# STM32F103_PCB.net
KiCad netlist of a schematic drawn in EAGLE
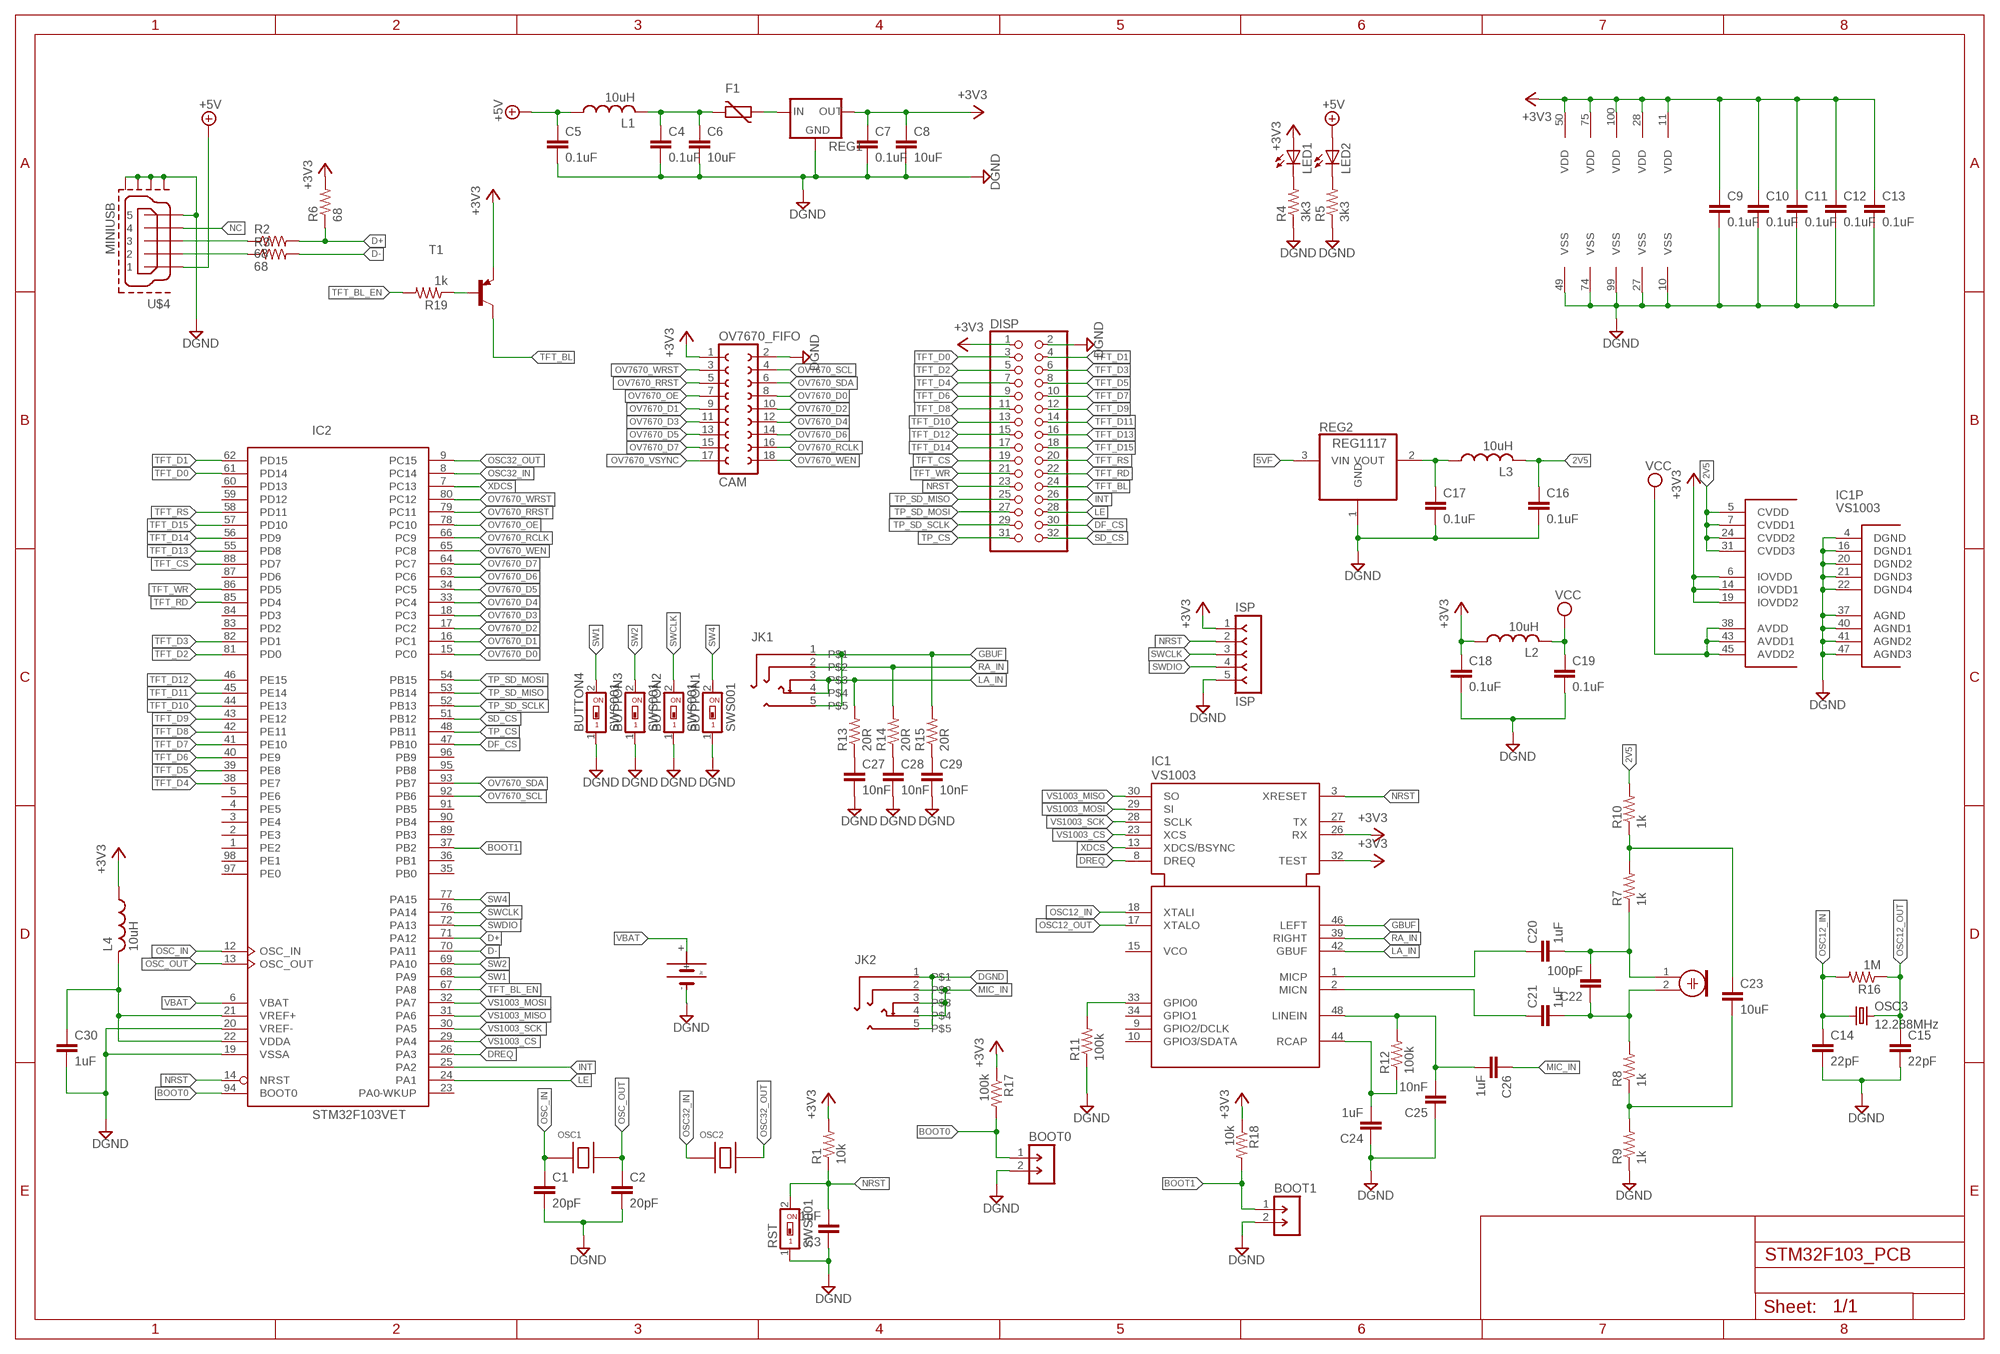
[diagram p0: schematic, sheet 1]

(export (version "E")
  (design (tool "Eeschema 10.0.6"))
  (components
    (comp (ref "BOOT0")
      (value "M-1X02-SIP-100-32")
      (footprint "eagle-import:SIP-100-02-32")
      (libsource (lib "eagle-import") (part "M-1X02-SIP-100-32"))
    )
    (comp (ref "BOOT1")
      (value "M-1X02-SIP-100-32")
      (footprint "eagle-import:SIP-100-02-32")
      (libsource (lib "eagle-import") (part "M-1X02-SIP-100-32"))
    )
    (comp (ref "BUTTON1")
      (value "SWS001")
      (footprint "eagle-import:SMS-001")
      (libsource (lib "eagle-import") (part "SWS001"))
    )
    (comp (ref "BUTTON2")
      (value "SWS001")
      (footprint "eagle-import:SMS-001")
      (libsource (lib "eagle-import") (part "SWS001"))
    )
    (comp (ref "BUTTON3")
      (value "SWS001")
      (footprint "eagle-import:SMS-001")
      (libsource (lib "eagle-import") (part "SWS001"))
    )
    (comp (ref "BUTTON4")
      (value "SWS001")
      (footprint "eagle-import:SMS-001")
      (libsource (lib "eagle-import") (part "SWS001"))
    )
    (comp (ref "C1")
      (value "20pF")
      (footprint "eagle-import:C1206")
      (libsource (lib "eagle-import") (part "C-EUC1206"))
    )
    (comp (ref "C2")
      (value "20pF")
      (footprint "eagle-import:C1206")
      (libsource (lib "eagle-import") (part "C-EUC1206"))
    )
    (comp (ref "C3")
      (value "1uF")
      (footprint "eagle-import:C1206")
      (libsource (lib "eagle-import") (part "C-EUC1206"))
    )
    (comp (ref "C4")
      (value "0.1uF")
      (footprint "eagle-import:C1206")
      (libsource (lib "eagle-import") (part "C-EUC1206"))
    )
    (comp (ref "C5")
      (value "0.1uF")
      (footprint "eagle-import:C1206")
      (libsource (lib "eagle-import") (part "C-EUC1206"))
    )
    (comp (ref "C6")
      (value "10uF")
      (footprint "eagle-import:C1206")
      (libsource (lib "eagle-import") (part "C-EUC1206"))
    )
    (comp (ref "C7")
      (value "0.1uF")
      (footprint "eagle-import:C1206")
      (libsource (lib "eagle-import") (part "C-EUC1206"))
    )
    (comp (ref "C8")
      (value "10uF")
      (footprint "eagle-import:C1206")
      (libsource (lib "eagle-import") (part "C-EUC1206"))
    )
    (comp (ref "C9")
      (value "0.1uF")
      (footprint "eagle-import:C1206")
      (libsource (lib "eagle-import") (part "C-EUC1206"))
    )
    (comp (ref "C10")
      (value "0.1uF")
      (footprint "eagle-import:C1206")
      (libsource (lib "eagle-import") (part "C-EUC1206"))
    )
    (comp (ref "C11")
      (value "0.1uF")
      (footprint "eagle-import:C1206")
      (libsource (lib "eagle-import") (part "C-EUC1206"))
    )
    (comp (ref "C12")
      (value "0.1uF")
      (footprint "eagle-import:C1206")
      (libsource (lib "eagle-import") (part "C-EUC1206"))
    )
    (comp (ref "C13")
      (value "0.1uF")
      (footprint "eagle-import:C1206")
      (libsource (lib "eagle-import") (part "C-EUC1206"))
    )
    (comp (ref "C14")
      (value "22pF")
      (footprint "eagle-import:C1206")
      (libsource (lib "eagle-import") (part "C-EUC1206"))
    )
    (comp (ref "C15")
      (value "22pF")
      (footprint "eagle-import:C1206")
      (libsource (lib "eagle-import") (part "C-EUC1206"))
    )
    (comp (ref "C16")
      (value "0.1uF")
      (footprint "eagle-import:C1206")
      (libsource (lib "eagle-import") (part "C-EUC1206"))
    )
    (comp (ref "C17")
      (value "0.1uF")
      (footprint "eagle-import:C1206")
      (libsource (lib "eagle-import") (part "C-EUC1206"))
    )
    (comp (ref "C18")
      (value "0.1uF")
      (footprint "eagle-import:C1206")
      (libsource (lib "eagle-import") (part "C-EUC1206"))
    )
    (comp (ref "C19")
      (value "0.1uF")
      (footprint "eagle-import:C1206")
      (libsource (lib "eagle-import") (part "C-EUC1206"))
    )
    (comp (ref "C20")
      (value "1uF")
      (footprint "eagle-import:C1206")
      (libsource (lib "eagle-import") (part "C-EUC1206"))
    )
    (comp (ref "C21")
      (value "1uF")
      (footprint "eagle-import:C1206")
      (libsource (lib "eagle-import") (part "C-EUC1206"))
    )
    (comp (ref "C22")
      (value "100pF")
      (footprint "eagle-import:C1206")
      (libsource (lib "eagle-import") (part "C-EUC1206"))
    )
    (comp (ref "C23")
      (value "10uF")
      (footprint "eagle-import:C1206")
      (libsource (lib "eagle-import") (part "C-EUC1206"))
    )
    (comp (ref "C24")
      (value "1uF")
      (footprint "eagle-import:C1206")
      (libsource (lib "eagle-import") (part "C-EUC1206"))
    )
    (comp (ref "C25")
      (value "10nF")
      (footprint "eagle-import:C1206")
      (libsource (lib "eagle-import") (part "C-EUC1206"))
    )
    (comp (ref "C26")
      (value "1uF")
      (footprint "eagle-import:C1206")
      (libsource (lib "eagle-import") (part "C-EUC1206"))
    )
    (comp (ref "C27")
      (value "10nF")
      (footprint "eagle-import:C1206")
      (libsource (lib "eagle-import") (part "C-EUC1206"))
    )
    (comp (ref "C28")
      (value "10nF")
      (footprint "eagle-import:C1206")
      (libsource (lib "eagle-import") (part "C-EUC1206"))
    )
    (comp (ref "C29")
      (value "10nF")
      (footprint "eagle-import:C1206")
      (libsource (lib "eagle-import") (part "C-EUC1206"))
    )
    (comp (ref "C30")
      (value "1uF")
      (footprint "eagle-import:C1206")
      (libsource (lib "eagle-import") (part "C-EUC1206"))
    )
    (comp (ref "CAM")
      (value "OV7670_FIFO")
      (footprint "eagle-import:FE09-2")
      (libsource (lib "eagle-import") (part "FE09-2"))
    )
    (comp (ref "DISP")
      (value "PINHD-2X16")
      (footprint "eagle-import:2X16")
      (libsource (lib "eagle-import") (part "PINHD-2X16"))
    )
    (comp (ref "F1")
      (value "VARISTORCN1206")
      (footprint "eagle-import:CT_CN1206")
      (libsource (lib "eagle-import") (part "VARISTORCN1206"))
    )
    (comp (ref "IC1")
      (value "VS1003")
      (footprint "eagle-import:LQFP48")
      (libsource (lib "eagle-import") (part "VS1003"))
    )
    (comp (ref "IC2")
      (value "STM32F103VET")
      (footprint "eagle-import:LQFP100")
      (libsource (lib "eagle-import") (part "STM32F103VTE"))
    )
    (comp (ref "ISP")
      (value "ISP")
      (footprint "eagle-import:SIP-100-05-40")
      (libsource (lib "eagle-import") (part "F-1X05-SIP-100-40"))
    )
    (comp (ref "JK1")
      (value "HEADPHONE_XXX1")
      (footprint "eagle-import:HEADPHONE_XXX1")
      (libsource (lib "eagle-import") (part "HEADPHONE_XXX1"))
    )
    (comp (ref "JK2")
      (value "HEADPHONE_XXX1")
      (footprint "eagle-import:HEADPHONE_XXX1")
      (libsource (lib "eagle-import") (part "HEADPHONE_XXX1"))
    )
    (comp (ref "L1")
      (value "10uH")
      (footprint "eagle-import:L3216C")
      (libsource (lib "eagle-import") (part "L-USL3216C"))
    )
    (comp (ref "L2")
      (value "10uH")
      (footprint "eagle-import:L3216C")
      (libsource (lib "eagle-import") (part "L-USL3216C"))
    )
    (comp (ref "L3")
      (value "10uH")
      (footprint "eagle-import:L3216C")
      (libsource (lib "eagle-import") (part "L-USL3216C"))
    )
    (comp (ref "L4")
      (value "10uH")
      (footprint "eagle-import:L3216C")
      (libsource (lib "eagle-import") (part "L-USL3216C"))
    )
    (comp (ref "LED1")
      (value "LEDSML1206")
      (footprint "eagle-import:SML1206")
      (libsource (lib "eagle-import") (part "LEDSML1206"))
    )
    (comp (ref "LED2")
      (value "LEDSML1206")
      (footprint "eagle-import:SML1206")
      (libsource (lib "eagle-import") (part "LEDSML1206"))
    )
    (comp (ref "MIC")
      (value "ELECTRET_MICROPHON-WM-61A")
      (footprint "eagle-import:WM-61A")
      (libsource (lib "eagle-import") (part "ELECTRET_MICROPHON-WM-61A"))
    )
    (comp (ref "OSC1")
      (value "8.0MHz")
      (footprint "eagle-import:IQG7050B")
      (libsource (lib "eagle-import") (part "SMCE-7050"))
    )
    (comp (ref "OSC2")
      (value "32.768kHz")
      (footprint "eagle-import:IQG5032A")
      (libsource (lib "eagle-import") (part "SMAQ-5032A"))
    )
    (comp (ref "OSC3")
      (value "12.288MHz")
      (footprint "eagle-import:HC49UP")
      (libsource (lib "eagle-import") (part "CRYSTALHC49UP"))
    )
    (comp (ref "R1")
      (value "10k")
      (footprint "eagle-import:R1206")
      (libsource (lib "eagle-import") (part "R-US_R1206"))
    )
    (comp (ref "R2")
      (value "68")
      (footprint "eagle-import:R1206")
      (libsource (lib "eagle-import") (part "R-US_R1206"))
    )
    (comp (ref "R3")
      (value "68")
      (footprint "eagle-import:R1206")
      (libsource (lib "eagle-import") (part "R-US_R1206"))
    )
    (comp (ref "R4")
      (value "3k3")
      (footprint "eagle-import:R1206")
      (libsource (lib "eagle-import") (part "R-US_R1206"))
    )
    (comp (ref "R5")
      (value "3k3")
      (footprint "eagle-import:R1206")
      (libsource (lib "eagle-import") (part "R-US_R1206"))
    )
    (comp (ref "R6")
      (value "68")
      (footprint "eagle-import:R1206")
      (libsource (lib "eagle-import") (part "R-US_R1206"))
    )
    (comp (ref "R7")
      (value "1k")
      (footprint "eagle-import:R1206")
      (libsource (lib "eagle-import") (part "R-US_R1206"))
    )
    (comp (ref "R8")
      (value "1k")
      (footprint "eagle-import:R1206")
      (libsource (lib "eagle-import") (part "R-US_R1206"))
    )
    (comp (ref "R9")
      (value "1k")
      (footprint "eagle-import:R1206")
      (libsource (lib "eagle-import") (part "R-US_R1206"))
    )
    (comp (ref "R10")
      (value "1k")
      (footprint "eagle-import:R1206")
      (libsource (lib "eagle-import") (part "R-US_R1206"))
    )
    (comp (ref "R11")
      (value "100k")
      (footprint "eagle-import:R1206")
      (libsource (lib "eagle-import") (part "R-US_R1206"))
    )
    (comp (ref "R12")
      (value "100k")
      (footprint "eagle-import:R1206")
      (libsource (lib "eagle-import") (part "R-US_R1206"))
    )
    (comp (ref "R13")
      (value "20R")
      (footprint "eagle-import:R1206")
      (libsource (lib "eagle-import") (part "R-US_R1206"))
    )
    (comp (ref "R14")
      (value "20R")
      (footprint "eagle-import:R1206")
      (libsource (lib "eagle-import") (part "R-US_R1206"))
    )
    (comp (ref "R15")
      (value "20R")
      (footprint "eagle-import:R1206")
      (libsource (lib "eagle-import") (part "R-US_R1206"))
    )
    (comp (ref "R16")
      (value "1M")
      (footprint "eagle-import:R1206")
      (libsource (lib "eagle-import") (part "R-US_R1206"))
    )
    (comp (ref "R17")
      (value "100k")
      (footprint "eagle-import:R1206")
      (libsource (lib "eagle-import") (part "R-US_R1206"))
    )
    (comp (ref "R18")
      (value "10k")
      (footprint "eagle-import:R1206")
      (libsource (lib "eagle-import") (part "R-US_R1206"))
    )
    (comp (ref "R19")
      (value "1k")
      (footprint "eagle-import:R1206")
      (libsource (lib "eagle-import") (part "R-US_R1206"))
    )
    (comp (ref "REG1")
      (value "XC63FPM")
      (footprint "eagle-import:SOT23")
      (libsource (lib "eagle-import") (part "XC63FPM"))
    )
    (comp (ref "REG2")
      (value "REG1117")
      (footprint "eagle-import:SOT223")
      (libsource (lib "eagle-import") (part "REG1117"))
    )
    (comp (ref "RST")
      (value "SWS001")
      (footprint "eagle-import:SMS-001")
      (libsource (lib "eagle-import") (part "SWS001"))
    )
    (comp (ref "T1")
      (value "MMBT3906LT1-PNP-SOT23-BEC")
      (footprint "eagle-import:SOT23-BEC")
      (libsource (lib "eagle-import") (part "-PNP-SOT23-BECMMBT3906LT1"))
    )
    (comp (ref "U$1")
      (value "1220BATTERY_SF")
      (footprint "eagle-import:1220BATTERY")
      (libsource (lib "eagle-import") (part "1220BATTERY_SF"))
    )
    (comp (ref "U$4")
      (value "MINIUSB")
      (footprint "eagle-import:MK5P")
      (libsource (lib "eagle-import") (part "MINIUSB"))
    )
  )
  (nets
    (net (code "1") (name "+3V3") (class "Default")
      (node (ref "C10") (pin "1") (pinfunction "1_1") (pintype "passive"))
      (node (ref "C11") (pin "1") (pinfunction "1_1") (pintype "passive"))
      (node (ref "C12") (pin "1") (pinfunction "1_1") (pintype "passive"))
      (node (ref "C13") (pin "1") (pinfunction "1_1") (pintype "passive"))
      (node (ref "C18") (pin "1") (pinfunction "1_1") (pintype "passive"))
      (node (ref "C7") (pin "1") (pinfunction "1_1") (pintype "passive"))
      (node (ref "C8") (pin "1") (pinfunction "1_1") (pintype "passive"))
      (node (ref "C9") (pin "1") (pinfunction "1_1") (pintype "passive"))
      (node (ref "CAM") (pin "1") (pinfunction "1_1") (pintype "passive"))
      (node (ref "DISP") (pin "1") (pinfunction "1_1") (pintype "passive"))
      (node (ref "IC1") (pin "14") (pinfunction "IOVDD1_14") (pintype "power_in"))
      (node (ref "IC1") (pin "19") (pinfunction "IOVDD2_19") (pintype "power_in"))
      (node (ref "IC1") (pin "26") (pinfunction "RX_26") (pintype "bidirectional"))
      (node (ref "IC1") (pin "32") (pinfunction "TEST_32") (pintype "bidirectional"))
      (node (ref "IC1") (pin "6") (pinfunction "IOVDD_6") (pintype "power_in"))
      (node (ref "IC2") (pin "100") (pinfunction "VDD_100") (pintype "power_in"))
      (node (ref "IC2") (pin "11") (pinfunction "VDD_11") (pintype "power_in"))
      (node (ref "IC2") (pin "28") (pinfunction "VDD_28") (pintype "power_in"))
      (node (ref "IC2") (pin "50") (pinfunction "VDD_50") (pintype "power_in"))
      (node (ref "IC2") (pin "75") (pinfunction "VDD_75") (pintype "power_in"))
      (node (ref "ISP") (pin "1") (pinfunction "1_1") (pintype "passive"))
      (node (ref "L2") (pin "1") (pinfunction "1_1") (pintype "passive"))
      (node (ref "L4") (pin "1") (pinfunction "1_1") (pintype "passive"))
      (node (ref "LED1") (pin "A") (pinfunction "A_A") (pintype "passive"))
      (node (ref "R1") (pin "2") (pinfunction "2_2") (pintype "passive"))
      (node (ref "R17") (pin "1") (pinfunction "1_1") (pintype "passive"))
      (node (ref "R18") (pin "1") (pinfunction "1_1") (pintype "passive"))
      (node (ref "R6") (pin "2") (pinfunction "2_2") (pintype "passive"))
      (node (ref "REG1") (pin "2") (pinfunction "OUT_2") (pintype "passive"))
      (node (ref "T1") (pin "E") (pinfunction "E_E") (pintype "passive"))
    )
    (net (code "2") (name "+5V") (class "Default")
      (node (ref "C5") (pin "1") (pinfunction "1_1") (pintype "passive"))
      (node (ref "L1") (pin "1") (pinfunction "1_1") (pintype "passive"))
      (node (ref "LED2") (pin "A") (pinfunction "A_A") (pintype "passive"))
      (node (ref "U$4") (pin "1") (pinfunction "1_1") (pintype "input"))
    )
    (net (code "3") (name "2V5") (class "Default")
      (node (ref "C16") (pin "1") (pinfunction "1_1") (pintype "passive"))
      (node (ref "IC1") (pin "24") (pinfunction "CVDD2_24") (pintype "power_in"))
      (node (ref "IC1") (pin "31") (pinfunction "CVDD3_31") (pintype "power_in"))
      (node (ref "IC1") (pin "5") (pinfunction "CVDD_5") (pintype "power_in"))
      (node (ref "IC1") (pin "7") (pinfunction "CVDD1_7") (pintype "power_in"))
      (node (ref "L3") (pin "2") (pinfunction "2_2") (pintype "passive"))
      (node (ref "R10") (pin "2") (pinfunction "2_2") (pintype "passive"))
    )
    (net (code "4") (name "5VF") (class "Default")
      (node (ref "F1") (pin "1") (pinfunction "1_1") (pintype "passive"))
      (node (ref "REG1") (pin "3") (pinfunction "IN_3") (pintype "input"))
      (node (ref "REG2") (pin "3") (pinfunction "VIN_3") (pintype "input"))
    )
    (net (code "5") (name "BOOT0") (class "Default")
      (node (ref "BOOT0") (pin "1") (pinfunction "1_1") (pintype "passive"))
      (node (ref "IC2") (pin "94") (pinfunction "BOOT0_94") (pintype "input"))
      (node (ref "R17") (pin "2") (pinfunction "2_2") (pintype "passive"))
    )
    (net (code "6") (name "BOOT1") (class "Default")
      (node (ref "BOOT1") (pin "1") (pinfunction "1_1") (pintype "passive"))
      (node (ref "IC2") (pin "37") (pinfunction "PB2_37") (pintype "bidirectional"))
      (node (ref "R18") (pin "2") (pinfunction "2_2") (pintype "passive"))
    )
    (net (code "7") (name "D+") (class "Default")
      (node (ref "IC2") (pin "71") (pinfunction "PA12_71") (pintype "bidirectional"))
      (node (ref "R2") (pin "2") (pinfunction "2_2") (pintype "passive"))
      (node (ref "R6") (pin "1") (pinfunction "1_1") (pintype "passive"))
    )
    (net (code "8") (name "D-") (class "Default")
      (node (ref "IC2") (pin "70") (pinfunction "PA11_70") (pintype "bidirectional"))
      (node (ref "R3") (pin "2") (pinfunction "2_2") (pintype "passive"))
    )
    (net (code "9") (name "DF_CS") (class "Default")
      (node (ref "DISP") (pin "30") (pinfunction "30_30") (pintype "passive"))
      (node (ref "IC2") (pin "47") (pinfunction "PB10_47") (pintype "bidirectional"))
    )
    (net (code "10") (name "DGND") (class "Default")
      (node (ref "BOOT0") (pin "2") (pinfunction "2_2") (pintype "passive"))
      (node (ref "BOOT1") (pin "2") (pinfunction "2_2") (pintype "passive"))
      (node (ref "BUTTON1") (pin "1") (pinfunction "1_1") (pintype "passive"))
      (node (ref "BUTTON2") (pin "1") (pinfunction "1_1") (pintype "passive"))
      (node (ref "BUTTON3") (pin "1") (pinfunction "1_1") (pintype "passive"))
      (node (ref "BUTTON4") (pin "1") (pinfunction "1_1") (pintype "passive"))
      (node (ref "C1") (pin "2") (pinfunction "2_2") (pintype "passive"))
      (node (ref "C10") (pin "2") (pinfunction "2_2") (pintype "passive"))
      (node (ref "C11") (pin "2") (pinfunction "2_2") (pintype "passive"))
      (node (ref "C12") (pin "2") (pinfunction "2_2") (pintype "passive"))
      (node (ref "C13") (pin "2") (pinfunction "2_2") (pintype "passive"))
      (node (ref "C14") (pin "2") (pinfunction "2_2") (pintype "passive"))
      (node (ref "C15") (pin "2") (pinfunction "2_2") (pintype "passive"))
      (node (ref "C16") (pin "2") (pinfunction "2_2") (pintype "passive"))
      (node (ref "C17") (pin "2") (pinfunction "2_2") (pintype "passive"))
      (node (ref "C18") (pin "2") (pinfunction "2_2") (pintype "passive"))
      (node (ref "C19") (pin "2") (pinfunction "2_2") (pintype "passive"))
      (node (ref "C2") (pin "2") (pinfunction "2_2") (pintype "passive"))
      (node (ref "C24") (pin "1") (pinfunction "1_1") (pintype "passive"))
      (node (ref "C25") (pin "1") (pinfunction "1_1") (pintype "passive"))
      (node (ref "C27") (pin "2") (pinfunction "2_2") (pintype "passive"))
      (node (ref "C28") (pin "2") (pinfunction "2_2") (pintype "passive"))
      (node (ref "C29") (pin "2") (pinfunction "2_2") (pintype "passive"))
      (node (ref "C3") (pin "1") (pinfunction "1_1") (pintype "passive"))
      (node (ref "C30") (pin "2") (pinfunction "2_2") (pintype "passive"))
      (node (ref "C4") (pin "2") (pinfunction "2_2") (pintype "passive"))
      (node (ref "C5") (pin "2") (pinfunction "2_2") (pintype "passive"))
      (node (ref "C6") (pin "2") (pinfunction "2_2") (pintype "passive"))
      (node (ref "C7") (pin "2") (pinfunction "2_2") (pintype "passive"))
      (node (ref "C8") (pin "2") (pinfunction "2_2") (pintype "passive"))
      (node (ref "C9") (pin "2") (pinfunction "2_2") (pintype "passive"))
      (node (ref "CAM") (pin "2") (pinfunction "2_2") (pintype "passive"))
      (node (ref "DISP") (pin "2") (pinfunction "2_2") (pintype "passive"))
      (node (ref "IC1") (pin "16") (pinfunction "DGND1_16") (pintype "power_in"))
      (node (ref "IC1") (pin "20") (pinfunction "DGND2_20") (pintype "power_in"))
      (node (ref "IC1") (pin "21") (pinfunction "DGND3_21") (pintype "power_in"))
      (node (ref "IC1") (pin "22") (pinfunction "DGND4_22") (pintype "power_in"))
      (node (ref "IC1") (pin "37") (pinfunction "AGND_37") (pintype "power_in"))
      (node (ref "IC1") (pin "4") (pinfunction "DGND_4") (pintype "power_in"))
      (node (ref "IC1") (pin "40") (pinfunction "AGND1_40") (pintype "power_in"))
      (node (ref "IC1") (pin "41") (pinfunction "AGND2_41") (pintype "power_in"))
      (node (ref "IC1") (pin "47") (pinfunction "AGND3_47") (pintype "power_in"))
      (node (ref "IC2") (pin "10") (pinfunction "VSS_10") (pintype "power_in"))
      (node (ref "IC2") (pin "19") (pinfunction "VSSA_19") (pintype "power_in"))
      (node (ref "IC2") (pin "20") (pinfunction "VREF-_20") (pintype "power_in"))
      (node (ref "IC2") (pin "27") (pinfunction "VSS_27") (pintype "power_in"))
      (node (ref "IC2") (pin "49") (pinfunction "VSS_49") (pintype "power_in"))
      (node (ref "IC2") (pin "74") (pinfunction "VSS_74") (pintype "power_in"))
      (node (ref "IC2") (pin "99") (pinfunction "VSS_99") (pintype "power_in"))
      (node (ref "ISP") (pin "5") (pinfunction "5_5") (pintype "passive"))
      (node (ref "JK2") (pin "1") (pinfunction "P$1_1") (pintype "bidirectional"))
      (node (ref "JK2") (pin "5") (pinfunction "P$5_5") (pintype "bidirectional"))
      (node (ref "R11") (pin "1") (pinfunction "1_1") (pintype "passive"))
      (node (ref "R4") (pin "1") (pinfunction "1_1") (pintype "passive"))
      (node (ref "R5") (pin "1") (pinfunction "1_1") (pintype "passive"))
      (node (ref "R9") (pin "1") (pinfunction "1_1") (pintype "passive"))
      (node (ref "REG1") (pin "1") (pinfunction "GND_1") (pintype "input"))
      (node (ref "REG2") (pin "1") (pinfunction "GND_1") (pintype "power_in"))
      (node (ref "RST") (pin "1") (pinfunction "1_1") (pintype "passive"))
      (node (ref "U$1") (pin "-") (pinfunction "-_-") (pintype "bidirectional"))
      (node (ref "U$4") (pin "5") (pinfunction "5_5") (pintype "input"))
      (node (ref "U$4") (pin "P$1") (pinfunction "GND1_P$1") (pintype "bidirectional"))
      (node (ref "U$4") (pin "P$2") (pinfunction "GND2_P$2") (pintype "bidirectional"))
      (node (ref "U$4") (pin "P$6") (pinfunction "GND3_P$6") (pintype "bidirectional"))
      (node (ref "U$4") (pin "P$7") (pinfunction "GND4_P$7") (pintype "bidirectional"))
    )
    (net (code "11") (name "DREQ") (class "Default")
      (node (ref "IC1") (pin "8") (pinfunction "DREQ_8") (pintype "bidirectional"))
      (node (ref "IC2") (pin "26") (pinfunction "PA3_26") (pintype "bidirectional"))
    )
    (net (code "12") (name "GBUF") (class "Default")
      (node (ref "IC1") (pin "46") (pinfunction "LEFT_46") (pintype "bidirectional"))
      (node (ref "JK1") (pin "1") (pinfunction "P$1_1") (pintype "bidirectional"))
      (node (ref "JK1") (pin "5") (pinfunction "P$5_5") (pintype "bidirectional"))
      (node (ref "R15") (pin "2") (pinfunction "2_2") (pintype "passive"))
    )
    (net (code "13") (name "INT") (class "Default")
      (node (ref "DISP") (pin "26") (pinfunction "26_26") (pintype "passive"))
      (node (ref "IC2") (pin "25") (pinfunction "PA2_25") (pintype "bidirectional"))
    )
    (net (code "14") (name "LA_IN") (class "Default")
      (node (ref "IC1") (pin "42") (pinfunction "GBUF_42") (pintype "bidirectional"))
      (node (ref "JK1") (pin "3") (pinfunction "P$3_3") (pintype "bidirectional"))
      (node (ref "JK1") (pin "4") (pinfunction "P$4_4") (pintype "bidirectional"))
      (node (ref "R13") (pin "2") (pinfunction "2_2") (pintype "passive"))
    )
    (net (code "15") (name "LE") (class "Default")
      (node (ref "DISP") (pin "28") (pinfunction "28_28") (pintype "passive"))
      (node (ref "IC2") (pin "24") (pinfunction "PA1_24") (pintype "bidirectional"))
    )
    (net (code "16") (name "MIC_IN") (class "Default")
      (node (ref "C26") (pin "1") (pinfunction "1_1") (pintype "passive"))
      (node (ref "JK2") (pin "2") (pinfunction "P$2_2") (pintype "bidirectional"))
      (node (ref "JK2") (pin "3") (pinfunction "P$3_3") (pintype "bidirectional"))
      (node (ref "JK2") (pin "4") (pinfunction "P$4_4") (pintype "bidirectional"))
    )
    (net (code "17") (name "NC") (class "Default")
      (node (ref "U$4") (pin "4") (pinfunction "4_4") (pintype "input"))
    )
    (net (code "18") (name "NRST") (class "Default")
      (node (ref "C3") (pin "2") (pinfunction "2_2") (pintype "passive"))
      (node (ref "DISP") (pin "23") (pinfunction "23_23") (pintype "passive"))
      (node (ref "IC1") (pin "3") (pinfunction "XRESET_3") (pintype "bidirectional"))
      (node (ref "IC2") (pin "14") (pinfunction "NRST_14") (pintype "bidirectional"))
      (node (ref "ISP") (pin "2") (pinfunction "2_2") (pintype "passive"))
      (node (ref "R1") (pin "1") (pinfunction "1_1") (pintype "passive"))
      (node (ref "RST") (pin "2") (pinfunction "2_2") (pintype "passive"))
    )
    (net (code "19") (name "Net-(C4-Pad1)") (class "Default")
      (node (ref "C4") (pin "1") (pinfunction "1_1") (pintype "passive"))
      (node (ref "C6") (pin "1") (pinfunction "1_1") (pintype "passive"))
      (node (ref "F1") (pin "2") (pinfunction "2_2") (pintype "passive"))
      (node (ref "L1") (pin "2") (pinfunction "2_2") (pintype "passive"))
    )
    (net (code "20") (name "Net-(C20-Pad2)") (class "Default")
      (node (ref "C20") (pin "2") (pinfunction "2_2") (pintype "passive"))
      (node (ref "C22") (pin "2") (pinfunction "2_2") (pintype "passive"))
      (node (ref "MIC") (pin "1") (pinfunction "1_1") (pintype "passive"))
      (node (ref "R7") (pin "1") (pinfunction "1_1") (pintype "passive"))
    )
    (net (code "21") (name "Net-(C21-Pad2)") (class "Default")
      (node (ref "C21") (pin "2") (pinfunction "2_2") (pintype "passive"))
      (node (ref "C22") (pin "1") (pinfunction "1_1") (pintype "passive"))
      (node (ref "MIC") (pin "2") (pinfunction "2_2") (pintype "passive"))
      (node (ref "R8") (pin "2") (pinfunction "2_2") (pintype "passive"))
    )
    (net (code "22") (name "Net-(C23-Pad1)") (class "Default")
      (node (ref "C23") (pin "1") (pinfunction "1_1") (pintype "passive"))
      (node (ref "R10") (pin "1") (pinfunction "1_1") (pintype "passive"))
      (node (ref "R7") (pin "2") (pinfunction "2_2") (pintype "passive"))
    )
    (net (code "23") (name "Net-(C23-Pad2)") (class "Default")
      (node (ref "C23") (pin "2") (pinfunction "2_2") (pintype "passive"))
      (node (ref "R8") (pin "1") (pinfunction "1_1") (pintype "passive"))
      (node (ref "R9") (pin "2") (pinfunction "2_2") (pintype "passive"))
    )
    (net (code "24") (name "Net-(C27-Pad1)") (class "Default")
      (node (ref "C27") (pin "1") (pinfunction "1_1") (pintype "passive"))
      (node (ref "R13") (pin "1") (pinfunction "1_1") (pintype "passive"))
    )
    (net (code "25") (name "Net-(C28-Pad1)") (class "Default")
      (node (ref "C28") (pin "1") (pinfunction "1_1") (pintype "passive"))
      (node (ref "R14") (pin "1") (pinfunction "1_1") (pintype "passive"))
    )
    (net (code "26") (name "Net-(C29-Pad1)") (class "Default")
      (node (ref "C29") (pin "1") (pinfunction "1_1") (pintype "passive"))
      (node (ref "R15") (pin "1") (pinfunction "1_1") (pintype "passive"))
    )
    (net (code "27") (name "Net-(IC1A-GPIO0)") (class "Default")
      (node (ref "IC1") (pin "33") (pinfunction "GPIO0_33") (pintype "bidirectional"))
      (node (ref "R11") (pin "2") (pinfunction "2_2") (pintype "passive"))
    )
    (net (code "28") (name "Net-(IC1A-LINEIN)") (class "Default")
      (node (ref "C25") (pin "2") (pinfunction "2_2") (pintype "passive"))
      (node (ref "C26") (pin "2") (pinfunction "2_2") (pintype "passive"))
      (node (ref "IC1") (pin "48") (pinfunction "LINEIN_48") (pintype "bidirectional"))
      (node (ref "R12") (pin "2") (pinfunction "2_2") (pintype "passive"))
    )
    (net (code "29") (name "Net-(IC1A-MICN)") (class "Default")
      (node (ref "C21") (pin "1") (pinfunction "1_1") (pintype "passive"))
      (node (ref "IC1") (pin "2") (pinfunction "MICN_2") (pintype "bidirectional"))
    )
    (net (code "30") (name "Net-(IC1A-MICP)") (class "Default")
      (node (ref "C20") (pin "1") (pinfunction "1_1") (pintype "passive"))
      (node (ref "IC1") (pin "1") (pinfunction "MICP_1") (pintype "bidirectional"))
    )
    (net (code "31") (name "Net-(IC1A-RCAP)") (class "Default")
      (node (ref "C24") (pin "2") (pinfunction "2_2") (pintype "passive"))
      (node (ref "IC1") (pin "44") (pinfunction "RCAP_44") (pintype "bidirectional"))
      (node (ref "R12") (pin "1") (pinfunction "1_1") (pintype "passive"))
    )
    (net (code "32") (name "Net-(IC2A-VDDA)") (class "Default")
      (node (ref "C30") (pin "1") (pinfunction "1_1") (pintype "passive"))
      (node (ref "IC2") (pin "21") (pinfunction "VREF+_21") (pintype "power_in"))
      (node (ref "IC2") (pin "22") (pinfunction "VDDA_22") (pintype "power_in"))
      (node (ref "L4") (pin "2") (pinfunction "2_2") (pintype "passive"))
    )
    (net (code "33") (name "Net-(LED1-PadC)") (class "Default")
      (node (ref "LED1") (pin "C") (pinfunction "C_C") (pintype "passive"))
      (node (ref "R4") (pin "2") (pinfunction "2_2") (pintype "passive"))
    )
    (net (code "34") (name "Net-(LED2-PadC)") (class "Default")
      (node (ref "LED2") (pin "C") (pinfunction "C_C") (pintype "passive"))
      (node (ref "R5") (pin "2") (pinfunction "2_2") (pintype "passive"))
    )
    (net (code "35") (name "Net-(R2-Pad1)") (class "Default")
      (node (ref "R2") (pin "1") (pinfunction "1_1") (pintype "passive"))
      (node (ref "U$4") (pin "3") (pinfunction "3_3") (pintype "input"))
    )
    (net (code "36") (name "Net-(R3-Pad1)") (class "Default")
      (node (ref "R3") (pin "1") (pinfunction "1_1") (pintype "passive"))
      (node (ref "U$4") (pin "2") (pinfunction "2_2") (pintype "input"))
    )
    (net (code "37") (name "Net-(R19-Pad1)") (class "Default")
      (node (ref "R19") (pin "1") (pinfunction "1_1") (pintype "passive"))
      (node (ref "T1") (pin "B") (pinfunction "B_B") (pintype "passive"))
    )
    (net (code "38") (name "Net-(REG2-VOUT)") (class "Default")
      (node (ref "C17") (pin "1") (pinfunction "1_1") (pintype "passive"))
      (node (ref "L3") (pin "1") (pinfunction "1_1") (pintype "passive"))
      (node (ref "REG2") (pin "2") (pinfunction "VOUT_2") (pintype "output"))
    )
    (net (code "39") (name "OSC12_IN") (class "Default")
      (node (ref "C14") (pin "1") (pinfunction "1_1") (pintype "passive"))
      (node (ref "IC1") (pin "18") (pinfunction "XTALI_18") (pintype "bidirectional"))
      (node (ref "OSC3") (pin "1") (pinfunction "1_1") (pintype "passive"))
      (node (ref "R16") (pin "2") (pinfunction "2_2") (pintype "passive"))
    )
    (net (code "40") (name "OSC12_OUT") (class "Default")
      (node (ref "C15") (pin "1") (pinfunction "1_1") (pintype "passive"))
      (node (ref "IC1") (pin "17") (pinfunction "XTALO_17") (pintype "bidirectional"))
      (node (ref "OSC3") (pin "2") (pinfunction "2_2") (pintype "passive"))
      (node (ref "R16") (pin "1") (pinfunction "1_1") (pintype "passive"))
    )
    (net (code "41") (name "OSC32_IN") (class "Default")
      (node (ref "IC2") (pin "8") (pinfunction "PC14_8") (pintype "bidirectional"))
      (node (ref "OSC2") (pin "P$1") (pinfunction "PIN1_P$1") (pintype "bidirectional"))
    )
    (net (code "42") (name "OSC32_OUT") (class "Default")
      (node (ref "IC2") (pin "9") (pinfunction "PC15_9") (pintype "bidirectional"))
      (node (ref "OSC2") (pin "P$2") (pinfunction "PIN2_P$2") (pintype "bidirectional"))
    )
    (net (code "43") (name "OSC_IN") (class "Default")
      (node (ref "C1") (pin "1") (pinfunction "1_1") (pintype "passive"))
      (node (ref "IC2") (pin "12") (pinfunction "OSC_IN_12") (pintype "bidirectional"))
      (node (ref "OSC1") (pin "P$1") (pinfunction "PIN1_P$1") (pintype "bidirectional"))
    )
    (net (code "44") (name "OSC_OUT") (class "Default")
      (node (ref "C2") (pin "1") (pinfunction "1_1") (pintype "passive"))
      (node (ref "IC2") (pin "13") (pinfunction "OSC_OUT_13") (pintype "bidirectional"))
      (node (ref "OSC1") (pin "P$3") (pinfunction "PIN2_P$3") (pintype "bidirectional"))
    )
    (net (code "45") (name "OV7670_D0") (class "Default")
      (node (ref "CAM") (pin "8") (pinfunction "8_8") (pintype "passive"))
      (node (ref "IC2") (pin "15") (pinfunction "PC0_15") (pintype "bidirectional"))
    )
    (net (code "46") (name "OV7670_D1") (class "Default")
      (node (ref "CAM") (pin "9") (pinfunction "9_9") (pintype "passive"))
      (node (ref "IC2") (pin "16") (pinfunction "PC1_16") (pintype "bidirectional"))
    )
    (net (code "47") (name "OV7670_D2") (class "Default")
      (node (ref "CAM") (pin "10") (pinfunction "10_10") (pintype "passive"))
      (node (ref "IC2") (pin "17") (pinfunction "PC2_17") (pintype "bidirectional"))
    )
    (net (code "48") (name "OV7670_D3") (class "Default")
      (node (ref "CAM") (pin "11") (pinfunction "11_11") (pintype "passive"))
      (node (ref "IC2") (pin "18") (pinfunction "PC3_18") (pintype "bidirectional"))
    )
    (net (code "49") (name "OV7670_D4") (class "Default")
      (node (ref "CAM") (pin "12") (pinfunction "12_12") (pintype "passive"))
      (node (ref "IC2") (pin "33") (pinfunction "PC4_33") (pintype "bidirectional"))
    )
    (net (code "50") (name "OV7670_D5") (class "Default")
      (node (ref "CAM") (pin "13") (pinfunction "13_13") (pintype "passive"))
      (node (ref "IC2") (pin "34") (pinfunction "PC5_34") (pintype "bidirectional"))
    )
    (net (code "51") (name "OV7670_D6") (class "Default")
      (node (ref "CAM") (pin "14") (pinfunction "14_14") (pintype "passive"))
      (node (ref "IC2") (pin "63") (pinfunction "PC6_63") (pintype "bidirectional"))
    )
    (net (code "52") (name "OV7670_D7") (class "Default")
      (node (ref "CAM") (pin "15") (pinfunction "15_15") (pintype "passive"))
      (node (ref "IC2") (pin "64") (pinfunction "PC7_64") (pintype "bidirectional"))
    )
    (net (code "53") (name "OV7670_OE") (class "Default")
      (node (ref "CAM") (pin "7") (pinfunction "7_7") (pintype "passive"))
      (node (ref "IC2") (pin "78") (pinfunction "PC10_78") (pintype "bidirectional"))
    )
    (net (code "54") (name "OV7670_RCLK") (class "Default")
      (node (ref "CAM") (pin "16") (pinfunction "16_16") (pintype "passive"))
      (node (ref "IC2") (pin "66") (pinfunction "PC9_66") (pintype "bidirectional"))
    )
    (net (code "55") (name "OV7670_RRST") (class "Default")
      (node (ref "CAM") (pin "5") (pinfunction "5_5") (pintype "passive"))
      (node (ref "IC2") (pin "79") (pinfunction "PC11_79") (pintype "bidirectional"))
    )
    (net (code "56") (name "OV7670_SCL") (class "Default")
      (node (ref "CAM") (pin "4") (pinfunction "4_4") (pintype "passive"))
      (node (ref "IC2") (pin "92") (pinfunction "PB6_92") (pintype "bidirectional"))
    )
    (net (code "57") (name "OV7670_SDA") (class "Default")
      (node (ref "CAM") (pin "6") (pinfunction "6_6") (pintype "passive"))
      (node (ref "IC2") (pin "93") (pinfunction "PB7_93") (pintype "bidirectional"))
    )
    (net (code "58") (name "OV7670_VSYNC") (class "Default")
      (node (ref "CAM") (pin "17") (pinfunction "17_17") (pintype "passive"))
    )
    (net (code "59") (name "OV7670_WEN") (class "Default")
      (node (ref "CAM") (pin "18") (pinfunction "18_18") (pintype "passive"))
      (node (ref "IC2") (pin "65") (pinfunction "PC8_65") (pintype "bidirectional"))
    )
    (net (code "60") (name "OV7670_WRST") (class "Default")
      (node (ref "CAM") (pin "3") (pinfunction "3_3") (pintype "passive"))
      (node (ref "IC2") (pin "80") (pinfunction "PC12_80") (pintype "bidirectional"))
    )
    (net (code "61") (name "RA_IN") (class "Default")
      (node (ref "IC1") (pin "39") (pinfunction "RIGHT_39") (pintype "bidirectional"))
      (node (ref "JK1") (pin "2") (pinfunction "P$2_2") (pintype "bidirectional"))
      (node (ref "R14") (pin "2") (pinfunction "2_2") (pintype "passive"))
    )
    (net (code "62") (name "SD_CS") (class "Default")
      (node (ref "DISP") (pin "32") (pinfunction "32_32") (pintype "passive"))
      (node (ref "IC2") (pin "51") (pinfunction "PB12_51") (pintype "bidirectional"))
    )
    (net (code "63") (name "SW1") (class "Default")
      (node (ref "BUTTON4") (pin "2") (pinfunction "2_2") (pintype "passive"))
      (node (ref "IC2") (pin "68") (pinfunction "PA9_68") (pintype "bidirectional"))
    )
    (net (code "64") (name "SW2") (class "Default")
      (node (ref "BUTTON3") (pin "2") (pinfunction "2_2") (pintype "passive"))
      (node (ref "IC2") (pin "69") (pinfunction "PA10_69") (pintype "bidirectional"))
    )
    (net (code "65") (name "SW4") (class "Default")
      (node (ref "BUTTON1") (pin "2") (pinfunction "2_2") (pintype "passive"))
      (node (ref "IC2") (pin "77") (pinfunction "PA15_77") (pintype "bidirectional"))
    )
    (net (code "66") (name "SWCLK") (class "Default")
      (node (ref "BUTTON2") (pin "2") (pinfunction "2_2") (pintype "passive"))
      (node (ref "IC2") (pin "76") (pinfunction "PA14_76") (pintype "bidirectional"))
      (node (ref "ISP") (pin "3") (pinfunction "3_3") (pintype "passive"))
    )
    (net (code "67") (name "SWDIO") (class "Default")
      (node (ref "IC2") (pin "72") (pinfunction "PA13_72") (pintype "bidirectional"))
      (node (ref "ISP") (pin "4") (pinfunction "4_4") (pintype "passive"))
    )
    (net (code "68") (name "TFT_BL") (class "Default")
      (node (ref "DISP") (pin "24") (pinfunction "24_24") (pintype "passive"))
      (node (ref "T1") (pin "C") (pinfunction "C_C") (pintype "passive"))
    )
    (net (code "69") (name "TFT_BL_EN") (class "Default")
      (node (ref "IC2") (pin "67") (pinfunction "PA8_67") (pintype "bidirectional"))
      (node (ref "R19") (pin "2") (pinfunction "2_2") (pintype "passive"))
    )
    (net (code "70") (name "TFT_CS") (class "Default")
      (node (ref "DISP") (pin "19") (pinfunction "19_19") (pintype "passive"))
      (node (ref "IC2") (pin "88") (pinfunction "PD7_88") (pintype "bidirectional"))
    )
    (net (code "71") (name "TFT_D0") (class "Default")
      (node (ref "DISP") (pin "3") (pinfunction "3_3") (pintype "passive"))
      (node (ref "IC2") (pin "61") (pinfunction "PD14_61") (pintype "bidirectional"))
    )
    (net (code "72") (name "TFT_D1") (class "Default")
      (node (ref "DISP") (pin "4") (pinfunction "4_4") (pintype "passive"))
      (node (ref "IC2") (pin "62") (pinfunction "PD15_62") (pintype "bidirectional"))
    )
    (net (code "73") (name "TFT_D2") (class "Default")
      (node (ref "DISP") (pin "5") (pinfunction "5_5") (pintype "passive"))
      (node (ref "IC2") (pin "81") (pinfunction "PD0_81") (pintype "bidirectional"))
    )
    (net (code "74") (name "TFT_D3") (class "Default")
      (node (ref "DISP") (pin "6") (pinfunction "6_6") (pintype "passive"))
      (node (ref "IC2") (pin "82") (pinfunction "PD1_82") (pintype "bidirectional"))
    )
    (net (code "75") (name "TFT_D4") (class "Default")
      (node (ref "DISP") (pin "7") (pinfunction "7_7") (pintype "passive"))
      (node (ref "IC2") (pin "38") (pinfunction "PE7_38") (pintype "bidirectional"))
    )
    (net (code "76") (name "TFT_D5") (class "Default")
      (node (ref "DISP") (pin "8") (pinfunction "8_8") (pintype "passive"))
      (node (ref "IC2") (pin "39") (pinfunction "PE8_39") (pintype "bidirectional"))
    )
    (net (code "77") (name "TFT_D6") (class "Default")
      (node (ref "DISP") (pin "9") (pinfunction "9_9") (pintype "passive"))
      (node (ref "IC2") (pin "40") (pinfunction "PE9_40") (pintype "bidirectional"))
    )
    (net (code "78") (name "TFT_D7") (class "Default")
      (node (ref "DISP") (pin "10") (pinfunction "10_10") (pintype "passive"))
      (node (ref "IC2") (pin "41") (pinfunction "PE10_41") (pintype "bidirectional"))
    )
    (net (code "79") (name "TFT_D8") (class "Default")
      (node (ref "DISP") (pin "11") (pinfunction "11_11") (pintype "passive"))
      (node (ref "IC2") (pin "42") (pinfunction "PE11_42") (pintype "bidirectional"))
    )
    (net (code "80") (name "TFT_D9") (class "Default")
      (node (ref "DISP") (pin "12") (pinfunction "12_12") (pintype "passive"))
      (node (ref "IC2") (pin "43") (pinfunction "PE12_43") (pintype "bidirectional"))
    )
    (net (code "81") (name "TFT_D10") (class "Default")
      (node (ref "DISP") (pin "13") (pinfunction "13_13") (pintype "passive"))
      (node (ref "IC2") (pin "44") (pinfunction "PE13_44") (pintype "bidirectional"))
    )
    (net (code "82") (name "TFT_D11") (class "Default")
      (node (ref "DISP") (pin "14") (pinfunction "14_14") (pintype "passive"))
      (node (ref "IC2") (pin "45") (pinfunction "PE14_45") (pintype "bidirectional"))
    )
    (net (code "83") (name "TFT_D12") (class "Default")
      (node (ref "DISP") (pin "15") (pinfunction "15_15") (pintype "passive"))
      (node (ref "IC2") (pin "46") (pinfunction "PE15_46") (pintype "bidirectional"))
    )
    (net (code "84") (name "TFT_D13") (class "Default")
      (node (ref "DISP") (pin "16") (pinfunction "16_16") (pintype "passive"))
      (node (ref "IC2") (pin "55") (pinfunction "PD8_55") (pintype "bidirectional"))
    )
    (net (code "85") (name "TFT_D14") (class "Default")
      (node (ref "DISP") (pin "17") (pinfunction "17_17") (pintype "passive"))
      (node (ref "IC2") (pin "56") (pinfunction "PD9_56") (pintype "bidirectional"))
    )
    (net (code "86") (name "TFT_D15") (class "Default")
      (node (ref "DISP") (pin "18") (pinfunction "18_18") (pintype "passive"))
      (node (ref "IC2") (pin "57") (pinfunction "PD10_57") (pintype "bidirectional"))
    )
    (net (code "87") (name "TFT_RD") (class "Default")
      (node (ref "DISP") (pin "22") (pinfunction "22_22") (pintype "passive"))
      (node (ref "IC2") (pin "85") (pinfunction "PD4_85") (pintype "bidirectional"))
    )
    (net (code "88") (name "TFT_RS") (class "Default")
      (node (ref "DISP") (pin "20") (pinfunction "20_20") (pintype "passive"))
      (node (ref "IC2") (pin "58") (pinfunction "PD11_58") (pintype "bidirectional"))
    )
    (net (code "89") (name "TFT_WR") (class "Default")
      (node (ref "DISP") (pin "21") (pinfunction "21_21") (pintype "passive"))
      (node (ref "IC2") (pin "86") (pinfunction "PD5_86") (pintype "bidirectional"))
    )
    (net (code "90") (name "TP_CS") (class "Default")
      (node (ref "DISP") (pin "31") (pinfunction "31_31") (pintype "passive"))
      (node (ref "IC2") (pin "48") (pinfunction "PB11_48") (pintype "bidirectional"))
    )
    (net (code "91") (name "TP_SD_MISO") (class "Default")
      (node (ref "DISP") (pin "25") (pinfunction "25_25") (pintype "passive"))
      (node (ref "IC2") (pin "53") (pinfunction "PB14_53") (pintype "bidirectional"))
    )
    (net (code "92") (name "TP_SD_MOSI") (class "Default")
      (node (ref "DISP") (pin "27") (pinfunction "27_27") (pintype "passive"))
      (node (ref "IC2") (pin "54") (pinfunction "PB15_54") (pintype "bidirectional"))
    )
    (net (code "93") (name "TP_SD_SCLK") (class "Default")
      (node (ref "DISP") (pin "29") (pinfunction "29_29") (pintype "passive"))
      (node (ref "IC2") (pin "52") (pinfunction "PB13_52") (pintype "bidirectional"))
    )
    (net (code "94") (name "VBAT") (class "Default")
      (node (ref "IC2") (pin "6") (pinfunction "VBAT_6") (pintype "power_in"))
      (node (ref "U$1") (pin "+") (pinfunction "+_+") (pintype "bidirectional"))
    )
    (net (code "95") (name "VCC") (class "Default")
      (node (ref "C19") (pin "1") (pinfunction "1_1") (pintype "passive"))
      (node (ref "IC1") (pin "38") (pinfunction "AVDD_38") (pintype "power_in"))
      (node (ref "IC1") (pin "43") (pinfunction "AVDD1_43") (pintype "power_in"))
      (node (ref "IC1") (pin "45") (pinfunction "AVDD2_45") (pintype "power_in"))
      (node (ref "L2") (pin "2") (pinfunction "2_2") (pintype "passive"))
    )
    (net (code "96") (name "VS1003_CS") (class "Default")
      (node (ref "IC1") (pin "23") (pinfunction "XCS_23") (pintype "bidirectional"))
      (node (ref "IC2") (pin "29") (pinfunction "PA4_29") (pintype "bidirectional"))
    )
    (net (code "97") (name "VS1003_MISO") (class "Default")
      (node (ref "IC1") (pin "30") (pinfunction "SO_30") (pintype "bidirectional"))
      (node (ref "IC2") (pin "31") (pinfunction "PA6_31") (pintype "bidirectional"))
    )
    (net (code "98") (name "VS1003_MOSI") (class "Default")
      (node (ref "IC1") (pin "29") (pinfunction "SI_29") (pintype "bidirectional"))
      (node (ref "IC2") (pin "32") (pinfunction "PA7_32") (pintype "bidirectional"))
    )
    (net (code "99") (name "VS1003_SCK") (class "Default")
      (node (ref "IC1") (pin "28") (pinfunction "SCLK_28") (pintype "bidirectional"))
      (node (ref "IC2") (pin "30") (pinfunction "PA5_30") (pintype "bidirectional"))
    )
    (net (code "100") (name "XDCS") (class "Default")
      (node (ref "IC1") (pin "13") (pinfunction "XDCS/BSYNC_13") (pintype "bidirectional"))
      (node (ref "IC2") (pin "7") (pinfunction "PC13_7") (pintype "bidirectional"))
    )
    (net (code "101") (name "unconnected-(IC1A-GPIO1-Pad34)") (class "Default")
      (node (ref "IC1") (pin "34") (pinfunction "GPIO1_34") (pintype "bidirectional"))
    )
    (net (code "102") (name "unconnected-(IC1A-GPIO2{slash}DCLK-Pad9)") (class "Default")
      (node (ref "IC1") (pin "9") (pinfunction "GPIO2/DCLK_9") (pintype "bidirectional"))
    )
    (net (code "103") (name "unconnected-(IC1A-GPIO3{slash}SDATA-Pad10)") (class "Default")
      (node (ref "IC1") (pin "10") (pinfunction "GPIO3/SDATA_10") (pintype "bidirectional"))
    )
    (net (code "104") (name "unconnected-(IC1A-TX-Pad27)") (class "Default")
      (node (ref "IC1") (pin "27") (pinfunction "TX_27") (pintype "bidirectional"))
    )
    (net (code "105") (name "unconnected-(IC1A-VCO-Pad15)") (class "Default")
      (node (ref "IC1") (pin "15") (pinfunction "VCO_15") (pintype "bidirectional"))
    )
    (net (code "106") (name "unconnected-(IC2A-PA0-WKUP-Pad23)") (class "Default")
      (node (ref "IC2") (pin "23") (pinfunction "PA0-WKUP_23") (pintype "bidirectional"))
    )
    (net (code "107") (name "unconnected-(IC2A-PB0-Pad35)") (class "Default")
      (node (ref "IC2") (pin "35") (pinfunction "PB0_35") (pintype "bidirectional"))
    )
    (net (code "108") (name "unconnected-(IC2A-PB1-Pad36)") (class "Default")
      (node (ref "IC2") (pin "36") (pinfunction "PB1_36") (pintype "bidirectional"))
    )
    (net (code "109") (name "unconnected-(IC2A-PB3-Pad89)") (class "Default")
      (node (ref "IC2") (pin "89") (pinfunction "PB3_89") (pintype "bidirectional"))
    )
    (net (code "110") (name "unconnected-(IC2A-PB4-Pad90)") (class "Default")
      (node (ref "IC2") (pin "90") (pinfunction "PB4_90") (pintype "bidirectional"))
    )
    (net (code "111") (name "unconnected-(IC2A-PB5-Pad91)") (class "Default")
      (node (ref "IC2") (pin "91") (pinfunction "PB5_91") (pintype "bidirectional"))
    )
    (net (code "112") (name "unconnected-(IC2A-PB8-Pad95)") (class "Default")
      (node (ref "IC2") (pin "95") (pinfunction "PB8_95") (pintype "bidirectional"))
    )
    (net (code "113") (name "unconnected-(IC2A-PB9-Pad96)") (class "Default")
      (node (ref "IC2") (pin "96") (pinfunction "PB9_96") (pintype "bidirectional"))
    )
    (net (code "114") (name "unconnected-(IC2A-PD2-Pad83)") (class "Default")
      (node (ref "IC2") (pin "83") (pinfunction "PD2_83") (pintype "bidirectional"))
    )
    (net (code "115") (name "unconnected-(IC2A-PD3-Pad84)") (class "Default")
      (node (ref "IC2") (pin "84") (pinfunction "PD3_84") (pintype "bidirectional"))
    )
    (net (code "116") (name "unconnected-(IC2A-PD6-Pad87)") (class "Default")
      (node (ref "IC2") (pin "87") (pinfunction "PD6_87") (pintype "bidirectional"))
    )
    (net (code "117") (name "unconnected-(IC2A-PD12-Pad59)") (class "Default")
      (node (ref "IC2") (pin "59") (pinfunction "PD12_59") (pintype "bidirectional"))
    )
    (net (code "118") (name "unconnected-(IC2A-PD13-Pad60)") (class "Default")
      (node (ref "IC2") (pin "60") (pinfunction "PD13_60") (pintype "bidirectional"))
    )
    (net (code "119") (name "unconnected-(IC2A-PE0-Pad97)") (class "Default")
      (node (ref "IC2") (pin "97") (pinfunction "PE0_97") (pintype "bidirectional"))
    )
    (net (code "120") (name "unconnected-(IC2A-PE1-Pad98)") (class "Default")
      (node (ref "IC2") (pin "98") (pinfunction "PE1_98") (pintype "bidirectional"))
    )
    (net (code "121") (name "unconnected-(IC2A-PE2-Pad1)") (class "Default")
      (node (ref "IC2") (pin "1") (pinfunction "PE2_1") (pintype "bidirectional"))
    )
    (net (code "122") (name "unconnected-(IC2A-PE3-Pad2)") (class "Default")
      (node (ref "IC2") (pin "2") (pinfunction "PE3_2") (pintype "bidirectional"))
    )
    (net (code "123") (name "unconnected-(IC2A-PE4-Pad3)") (class "Default")
      (node (ref "IC2") (pin "3") (pinfunction "PE4_3") (pintype "bidirectional"))
    )
    (net (code "124") (name "unconnected-(IC2A-PE5-Pad4)") (class "Default")
      (node (ref "IC2") (pin "4") (pinfunction "PE5_4") (pintype "bidirectional"))
    )
    (net (code "125") (name "unconnected-(IC2A-PE6-Pad5)") (class "Default")
      (node (ref "IC2") (pin "5") (pinfunction "PE6_5") (pintype "bidirectional"))
    )
  )
)
